# Schematic.net
KiCad netlist of a schematic drawn in EAGLE
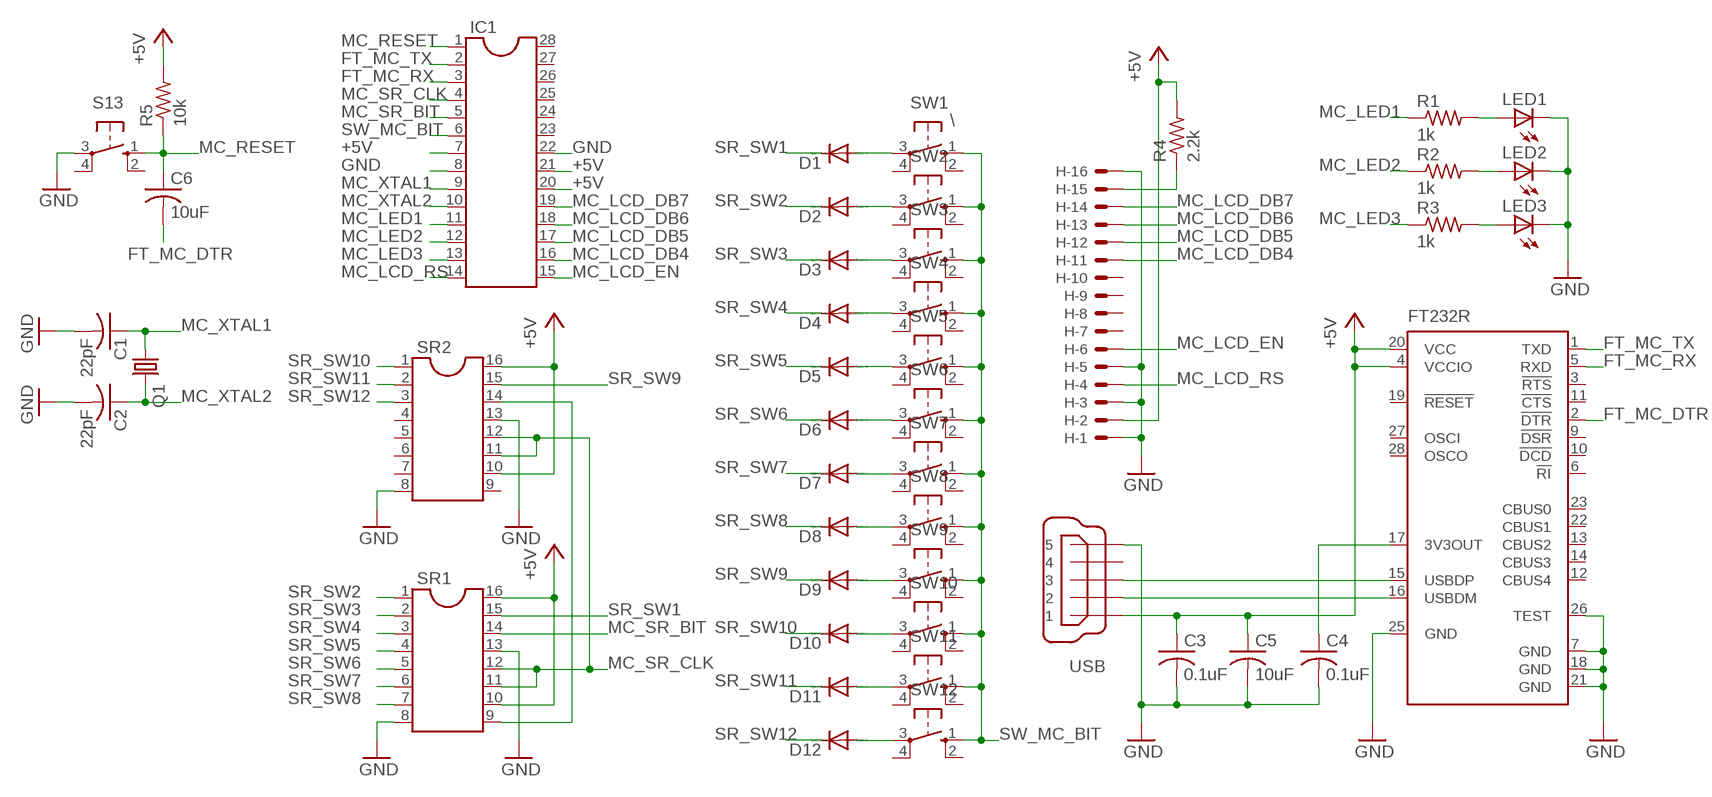
[diagram p0: schematic, sheet 1]

(export (version "E")
  (design (tool "Eeschema 10.0.6"))
  (components
    (comp (ref "C1")
      (value "22pF")
      (footprint "eagle-import:C025-024X044")
      (libsource (lib "eagle-import") (part "C-US025-024X044"))
    )
    (comp (ref "C2")
      (value "22pF")
      (footprint "eagle-import:C025-024X044")
      (libsource (lib "eagle-import") (part "C-US025-024X044"))
    )
    (comp (ref "C3")
      (value "0.1uF")
      (footprint "eagle-import:C025-024X044")
      (libsource (lib "eagle-import") (part "C-US025-024X044"))
    )
    (comp (ref "C4")
      (value "0.1uF")
      (footprint "eagle-import:C025-024X044")
      (libsource (lib "eagle-import") (part "C-US025-024X044"))
    )
    (comp (ref "C5")
      (value "10uF")
      (footprint "eagle-import:C025-024X044")
      (libsource (lib "eagle-import") (part "C-US025-024X044"))
    )
    (comp (ref "C6")
      (value "10uF")
      (footprint "eagle-import:C025-024X044")
      (libsource (lib "eagle-import") (part "C-US025-024X044"))
    )
    (comp (ref "D1")
      (value "DIODE-DO35-10")
      (footprint "eagle-import:DO35-10")
      (libsource (lib "eagle-import") (part "DIODE-DO35-10"))
    )
    (comp (ref "D2")
      (value "DIODE-DO35-10")
      (footprint "eagle-import:DO35-10")
      (libsource (lib "eagle-import") (part "DIODE-DO35-10"))
    )
    (comp (ref "D3")
      (value "DIODE-DO35-10")
      (footprint "eagle-import:DO35-10")
      (libsource (lib "eagle-import") (part "DIODE-DO35-10"))
    )
    (comp (ref "D4")
      (value "DIODE-DO35-10")
      (footprint "eagle-import:DO35-10")
      (libsource (lib "eagle-import") (part "DIODE-DO35-10"))
    )
    (comp (ref "D5")
      (value "DIODE-DO35-10")
      (footprint "eagle-import:DO35-10")
      (libsource (lib "eagle-import") (part "DIODE-DO35-10"))
    )
    (comp (ref "D6")
      (value "DIODE-DO35-10")
      (footprint "eagle-import:DO35-10")
      (libsource (lib "eagle-import") (part "DIODE-DO35-10"))
    )
    (comp (ref "D7")
      (value "DIODE-DO35-10")
      (footprint "eagle-import:DO35-10")
      (libsource (lib "eagle-import") (part "DIODE-DO35-10"))
    )
    (comp (ref "D8")
      (value "DIODE-DO35-10")
      (footprint "eagle-import:DO35-10")
      (libsource (lib "eagle-import") (part "DIODE-DO35-10"))
    )
    (comp (ref "D9")
      (value "DIODE-DO35-10")
      (footprint "eagle-import:DO35-10")
      (libsource (lib "eagle-import") (part "DIODE-DO35-10"))
    )
    (comp (ref "D10")
      (value "DIODE-DO35-10")
      (footprint "eagle-import:DO35-10")
      (libsource (lib "eagle-import") (part "DIODE-DO35-10"))
    )
    (comp (ref "D11")
      (value "DIODE-DO35-10")
      (footprint "eagle-import:DO35-10")
      (libsource (lib "eagle-import") (part "DIODE-DO35-10"))
    )
    (comp (ref "D12")
      (value "DIODE-DO35-10")
      (footprint "eagle-import:DO35-10")
      (libsource (lib "eagle-import") (part "DIODE-DO35-10"))
    )
    (comp (ref "FT232R")
      (value "FT232RL")
      (footprint "eagle-import:SSOP28")
      (libsource (lib "eagle-import") (part "FT232RL"))
    )
    (comp (ref "H")
      (value "C-GRID-16-70543")
      (footprint "eagle-import:70543-16")
      (libsource (lib "eagle-import") (part "C-GRID-16-70543"))
    )
    (comp (ref "IC1")
      (value "DIL28-3")
      (footprint "eagle-import:DIL28-3")
      (libsource (lib "eagle-import") (part "DIL28-3"))
    )
    (comp (ref "LED1")
      (value "LED3MM")
      (footprint "eagle-import:LED3MM")
      (libsource (lib "eagle-import") (part "LED3MM"))
    )
    (comp (ref "LED2")
      (value "LED3MM")
      (footprint "eagle-import:LED3MM")
      (libsource (lib "eagle-import") (part "LED3MM"))
    )
    (comp (ref "LED3")
      (value "LED3MM")
      (footprint "eagle-import:LED3MM")
      (libsource (lib "eagle-import") (part "LED3MM"))
    )
    (comp (ref "Q1")
      (value "CRYSTALHC49U-V")
      (footprint "eagle-import:HC49U-V")
      (libsource (lib "eagle-import") (part "CRYSTALHC49U-V"))
    )
    (comp (ref "R1")
      (value "1k")
      (footprint "eagle-import:0204V")
      (libsource (lib "eagle-import") (part "R-US_0204/2V"))
    )
    (comp (ref "R2")
      (value "1k")
      (footprint "eagle-import:0204V")
      (libsource (lib "eagle-import") (part "R-US_0204/2V"))
    )
    (comp (ref "R3")
      (value "1k")
      (footprint "eagle-import:0204V")
      (libsource (lib "eagle-import") (part "R-US_0204/2V"))
    )
    (comp (ref "R4")
      (value "2.2k")
      (footprint "eagle-import:0204V")
      (libsource (lib "eagle-import") (part "R-US_0204/2V"))
    )
    (comp (ref "R5")
      (value "10k")
      (footprint "eagle-import:0204V")
      (libsource (lib "eagle-import") (part "R-US_0204/2V"))
    )
    (comp (ref "S13")
      (value "10-XX")
      (footprint "eagle-import:B3F-10XX")
      (fields (field (name "MPN") "B3F-1000"))
      (libsource (lib "eagle-import") (part "10-XX"))
    )
    (comp (ref "SR1")
      (value "DIL16")
      (footprint "eagle-import:DIL16")
      (libsource (lib "eagle-import") (part "DIL16"))
    )
    (comp (ref "SR2")
      (value "DIL16")
      (footprint "eagle-import:DIL16")
      (libsource (lib "eagle-import") (part "DIL16"))
    )
    (comp (ref "SW1")
      (value "\\")
      (footprint "eagle-import:B3F-10XX")
      (fields (field (name "MPN") "B3F-1000"))
      (libsource (lib "eagle-import") (part "10-XX"))
    )
    (comp (ref "SW2")
      (value "10-XX")
      (footprint "eagle-import:B3F-10XX")
      (fields (field (name "MPN") "B3F-1000"))
      (libsource (lib "eagle-import") (part "10-XX"))
    )
    (comp (ref "SW3")
      (value "10-XX")
      (footprint "eagle-import:B3F-10XX")
      (fields (field (name "MPN") "B3F-1000"))
      (libsource (lib "eagle-import") (part "10-XX"))
    )
    (comp (ref "SW4")
      (value "10-XX")
      (footprint "eagle-import:B3F-10XX")
      (fields (field (name "MPN") "B3F-1000"))
      (libsource (lib "eagle-import") (part "10-XX"))
    )
    (comp (ref "SW5")
      (value "10-XX")
      (footprint "eagle-import:B3F-10XX")
      (fields (field (name "MPN") "B3F-1000"))
      (libsource (lib "eagle-import") (part "10-XX"))
    )
    (comp (ref "SW6")
      (value "10-XX")
      (footprint "eagle-import:B3F-10XX")
      (fields (field (name "MPN") "B3F-1000"))
      (libsource (lib "eagle-import") (part "10-XX"))
    )
    (comp (ref "SW7")
      (value "10-XX")
      (footprint "eagle-import:B3F-10XX")
      (fields (field (name "MPN") "B3F-1000"))
      (libsource (lib "eagle-import") (part "10-XX"))
    )
    (comp (ref "SW8")
      (value "10-XX")
      (footprint "eagle-import:B3F-10XX")
      (fields (field (name "MPN") "B3F-1000"))
      (libsource (lib "eagle-import") (part "10-XX"))
    )
    (comp (ref "SW9")
      (value "10-XX")
      (footprint "eagle-import:B3F-10XX")
      (fields (field (name "MPN") "B3F-1000"))
      (libsource (lib "eagle-import") (part "10-XX"))
    )
    (comp (ref "SW10")
      (value "10-XX")
      (footprint "eagle-import:B3F-10XX")
      (fields (field (name "MPN") "B3F-1000"))
      (libsource (lib "eagle-import") (part "10-XX"))
    )
    (comp (ref "SW11")
      (value "10-XX")
      (footprint "eagle-import:B3F-10XX")
      (fields (field (name "MPN") "B3F-1000"))
      (libsource (lib "eagle-import") (part "10-XX"))
    )
    (comp (ref "SW12")
      (value "10-XX")
      (footprint "eagle-import:B3F-10XX")
      (fields (field (name "MPN") "B3F-1000"))
      (libsource (lib "eagle-import") (part "10-XX"))
    )
    (comp (ref "USB")
      (value "MINI-USB_SHIELD5P2-32005-601")
      (footprint "eagle-import:32005-601")
      (libsource (lib "eagle-import") (part "MINI-USB_SHIELD5P2-32005-601"))
    )
  )
  (nets
    (net (code "1") (name "+5V") (class "Default")
      (node (ref "C3") (pin "1") (pinfunction "1_1") (pintype "passive"))
      (node (ref "C5") (pin "1") (pinfunction "1_1") (pintype "passive"))
      (node (ref "FT232R") (pin "20") (pinfunction "VCC_20") (pintype "power_in"))
      (node (ref "FT232R") (pin "4") (pinfunction "VCCIO_4") (pintype "power_in"))
      (node (ref "H") (pin "2") (pinfunction "S_2") (pintype "passive"))
      (node (ref "IC1") (pin "20") (pinfunction "20_20") (pintype "passive"))
      (node (ref "IC1") (pin "21") (pinfunction "21_21") (pintype "passive"))
      (node (ref "IC1") (pin "7") (pinfunction "7_7") (pintype "passive"))
      (node (ref "R4") (pin "2") (pinfunction "2_2") (pintype "passive"))
      (node (ref "R5") (pin "2") (pinfunction "2_2") (pintype "passive"))
      (node (ref "SR1") (pin "10") (pinfunction "10_10") (pintype "passive"))
      (node (ref "SR1") (pin "16") (pinfunction "16_16") (pintype "passive"))
      (node (ref "SR2") (pin "10") (pinfunction "10_10") (pintype "passive"))
      (node (ref "SR2") (pin "16") (pinfunction "16_16") (pintype "passive"))
      (node (ref "USB") (pin "1") (pinfunction "1_1") (pintype "passive"))
    )
    (net (code "2") (name "/FT_MC_DTR") (class "Default")
      (node (ref "C6") (pin "2") (pinfunction "2_2") (pintype "passive"))
      (node (ref "FT232R") (pin "2") (pinfunction "~{DTR}_2") (pintype "output"))
    )
    (net (code "3") (name "/FT_MC_RX") (class "Default")
      (node (ref "FT232R") (pin "5") (pinfunction "RXD_5") (pintype "input"))
      (node (ref "IC1") (pin "3") (pinfunction "3_3") (pintype "passive"))
    )
    (net (code "4") (name "/FT_MC_TX") (class "Default")
      (node (ref "FT232R") (pin "1") (pinfunction "TXD_1") (pintype "output"))
      (node (ref "IC1") (pin "2") (pinfunction "2_2") (pintype "passive"))
    )
    (net (code "5") (name "/MC_LCD_DB4") (class "Default")
      (node (ref "H") (pin "11") (pinfunction "S_11") (pintype "passive"))
      (node (ref "IC1") (pin "16") (pinfunction "16_16") (pintype "passive"))
    )
    (net (code "6") (name "/MC_LCD_DB5") (class "Default")
      (node (ref "H") (pin "12") (pinfunction "S_12") (pintype "passive"))
      (node (ref "IC1") (pin "17") (pinfunction "17_17") (pintype "passive"))
    )
    (net (code "7") (name "/MC_LCD_DB6") (class "Default")
      (node (ref "H") (pin "13") (pinfunction "S_13") (pintype "passive"))
      (node (ref "IC1") (pin "18") (pinfunction "18_18") (pintype "passive"))
    )
    (net (code "8") (name "/MC_LCD_DB7") (class "Default")
      (node (ref "H") (pin "14") (pinfunction "S_14") (pintype "passive"))
      (node (ref "IC1") (pin "19") (pinfunction "19_19") (pintype "passive"))
    )
    (net (code "9") (name "/MC_LCD_EN") (class "Default")
      (node (ref "H") (pin "6") (pinfunction "S_6") (pintype "passive"))
      (node (ref "IC1") (pin "15") (pinfunction "15_15") (pintype "passive"))
    )
    (net (code "10") (name "/MC_LCD_RS") (class "Default")
      (node (ref "H") (pin "4") (pinfunction "S_4") (pintype "passive"))
      (node (ref "IC1") (pin "14") (pinfunction "14_14") (pintype "passive"))
    )
    (net (code "11") (name "/MC_LED1") (class "Default")
      (node (ref "IC1") (pin "11") (pinfunction "11_11") (pintype "passive"))
      (node (ref "R1") (pin "1") (pinfunction "1_1") (pintype "passive"))
    )
    (net (code "12") (name "/MC_LED2") (class "Default")
      (node (ref "IC1") (pin "12") (pinfunction "12_12") (pintype "passive"))
      (node (ref "R2") (pin "1") (pinfunction "1_1") (pintype "passive"))
    )
    (net (code "13") (name "/MC_LED3") (class "Default")
      (node (ref "IC1") (pin "13") (pinfunction "13_13") (pintype "passive"))
      (node (ref "R3") (pin "1") (pinfunction "1_1") (pintype "passive"))
    )
    (net (code "14") (name "/MC_RESET") (class "Default")
      (node (ref "C6") (pin "1") (pinfunction "1_1") (pintype "passive"))
      (node (ref "IC1") (pin "1") (pinfunction "1_1") (pintype "passive"))
      (node (ref "R5") (pin "1") (pinfunction "1_1") (pintype "passive"))
      (node (ref "S13") (pin "1") (pinfunction "S_1") (pintype "passive"))
    )
    (net (code "15") (name "/MC_SR_BIT") (class "Default")
      (node (ref "IC1") (pin "5") (pinfunction "5_5") (pintype "passive"))
      (node (ref "SR1") (pin "14") (pinfunction "14_14") (pintype "passive"))
    )
    (net (code "16") (name "/MC_SR_CLK") (class "Default")
      (node (ref "IC1") (pin "4") (pinfunction "4_4") (pintype "passive"))
      (node (ref "SR1") (pin "11") (pinfunction "11_11") (pintype "passive"))
      (node (ref "SR1") (pin "12") (pinfunction "12_12") (pintype "passive"))
      (node (ref "SR2") (pin "11") (pinfunction "11_11") (pintype "passive"))
      (node (ref "SR2") (pin "12") (pinfunction "12_12") (pintype "passive"))
    )
    (net (code "17") (name "/MC_XTAL1") (class "Default")
      (node (ref "C1") (pin "1") (pinfunction "1_1") (pintype "passive"))
      (node (ref "IC1") (pin "9") (pinfunction "9_9") (pintype "passive"))
      (node (ref "Q1") (pin "1") (pinfunction "1_1") (pintype "passive"))
    )
    (net (code "18") (name "/MC_XTAL2") (class "Default")
      (node (ref "C2") (pin "1") (pinfunction "1_1") (pintype "passive"))
      (node (ref "IC1") (pin "10") (pinfunction "10_10") (pintype "passive"))
      (node (ref "Q1") (pin "2") (pinfunction "2_2") (pintype "passive"))
    )
    (net (code "19") (name "/SR_SW1") (class "Default")
      (node (ref "D1") (pin "C") (pinfunction "C_C") (pintype "passive"))
      (node (ref "SR1") (pin "15") (pinfunction "15_15") (pintype "passive"))
    )
    (net (code "20") (name "/SR_SW2") (class "Default")
      (node (ref "D2") (pin "C") (pinfunction "C_C") (pintype "passive"))
      (node (ref "SR1") (pin "1") (pinfunction "1_1") (pintype "passive"))
    )
    (net (code "21") (name "/SR_SW3") (class "Default")
      (node (ref "D3") (pin "C") (pinfunction "C_C") (pintype "passive"))
      (node (ref "SR1") (pin "2") (pinfunction "2_2") (pintype "passive"))
    )
    (net (code "22") (name "/SR_SW4") (class "Default")
      (node (ref "D4") (pin "C") (pinfunction "C_C") (pintype "passive"))
      (node (ref "SR1") (pin "3") (pinfunction "3_3") (pintype "passive"))
    )
    (net (code "23") (name "/SR_SW5") (class "Default")
      (node (ref "D5") (pin "C") (pinfunction "C_C") (pintype "passive"))
      (node (ref "SR1") (pin "4") (pinfunction "4_4") (pintype "passive"))
    )
    (net (code "24") (name "/SR_SW6") (class "Default")
      (node (ref "D6") (pin "C") (pinfunction "C_C") (pintype "passive"))
      (node (ref "SR1") (pin "5") (pinfunction "5_5") (pintype "passive"))
    )
    (net (code "25") (name "/SR_SW7") (class "Default")
      (node (ref "D7") (pin "C") (pinfunction "C_C") (pintype "passive"))
      (node (ref "SR1") (pin "6") (pinfunction "6_6") (pintype "passive"))
    )
    (net (code "26") (name "/SR_SW8") (class "Default")
      (node (ref "D8") (pin "C") (pinfunction "C_C") (pintype "passive"))
      (node (ref "SR1") (pin "7") (pinfunction "7_7") (pintype "passive"))
    )
    (net (code "27") (name "/SR_SW9") (class "Default")
      (node (ref "D9") (pin "C") (pinfunction "C_C") (pintype "passive"))
      (node (ref "SR2") (pin "15") (pinfunction "15_15") (pintype "passive"))
    )
    (net (code "28") (name "/SR_SW10") (class "Default")
      (node (ref "D10") (pin "C") (pinfunction "C_C") (pintype "passive"))
      (node (ref "SR2") (pin "1") (pinfunction "1_1") (pintype "passive"))
    )
    (net (code "29") (name "/SR_SW11") (class "Default")
      (node (ref "D11") (pin "C") (pinfunction "C_C") (pintype "passive"))
      (node (ref "SR2") (pin "2") (pinfunction "2_2") (pintype "passive"))
    )
    (net (code "30") (name "/SR_SW12") (class "Default")
      (node (ref "D12") (pin "C") (pinfunction "C_C") (pintype "passive"))
      (node (ref "SR2") (pin "3") (pinfunction "3_3") (pintype "passive"))
    )
    (net (code "31") (name "/SW_MC_BIT") (class "Default")
      (node (ref "IC1") (pin "6") (pinfunction "6_6") (pintype "passive"))
      (node (ref "SW1") (pin "1") (pinfunction "S_1") (pintype "passive"))
      (node (ref "SW10") (pin "1") (pinfunction "S_1") (pintype "passive"))
      (node (ref "SW11") (pin "1") (pinfunction "S_1") (pintype "passive"))
      (node (ref "SW12") (pin "1") (pinfunction "S_1") (pintype "passive"))
      (node (ref "SW2") (pin "1") (pinfunction "S_1") (pintype "passive"))
      (node (ref "SW3") (pin "1") (pinfunction "S_1") (pintype "passive"))
      (node (ref "SW4") (pin "1") (pinfunction "S_1") (pintype "passive"))
      (node (ref "SW5") (pin "1") (pinfunction "S_1") (pintype "passive"))
      (node (ref "SW6") (pin "1") (pinfunction "S_1") (pintype "passive"))
      (node (ref "SW7") (pin "1") (pinfunction "S_1") (pintype "passive"))
      (node (ref "SW8") (pin "1") (pinfunction "S_1") (pintype "passive"))
      (node (ref "SW9") (pin "1") (pinfunction "S_1") (pintype "passive"))
    )
    (net (code "32") (name "GND") (class "Default")
      (node (ref "C1") (pin "2") (pinfunction "2_2") (pintype "passive"))
      (node (ref "C2") (pin "2") (pinfunction "2_2") (pintype "passive"))
      (node (ref "C3") (pin "2") (pinfunction "2_2") (pintype "passive"))
      (node (ref "C4") (pin "2") (pinfunction "2_2") (pintype "passive"))
      (node (ref "C5") (pin "2") (pinfunction "2_2") (pintype "passive"))
      (node (ref "FT232R") (pin "18") (pinfunction "GND_18") (pintype "power_in"))
      (node (ref "FT232R") (pin "21") (pinfunction "GND_21") (pintype "power_in"))
      (node (ref "FT232R") (pin "25") (pinfunction "GND_25") (pintype "power_in"))
      (node (ref "FT232R") (pin "26") (pinfunction "TEST_26") (pintype "input"))
      (node (ref "FT232R") (pin "7") (pinfunction "GND_7") (pintype "power_in"))
      (node (ref "H") (pin "1") (pinfunction "S_1") (pintype "passive"))
      (node (ref "H") (pin "16") (pinfunction "S_16") (pintype "passive"))
      (node (ref "H") (pin "3") (pinfunction "S_3") (pintype "passive"))
      (node (ref "H") (pin "5") (pinfunction "S_5") (pintype "passive"))
      (node (ref "IC1") (pin "22") (pinfunction "22_22") (pintype "passive"))
      (node (ref "IC1") (pin "8") (pinfunction "8_8") (pintype "passive"))
      (node (ref "LED1") (pin "K") (pinfunction "C_K") (pintype "passive"))
      (node (ref "LED2") (pin "K") (pinfunction "C_K") (pintype "passive"))
      (node (ref "LED3") (pin "K") (pinfunction "C_K") (pintype "passive"))
      (node (ref "S13") (pin "3") (pinfunction "P_3") (pintype "passive"))
      (node (ref "SR1") (pin "13") (pinfunction "13_13") (pintype "passive"))
      (node (ref "SR1") (pin "8") (pinfunction "8_8") (pintype "passive"))
      (node (ref "SR2") (pin "13") (pinfunction "13_13") (pintype "passive"))
      (node (ref "SR2") (pin "8") (pinfunction "8_8") (pintype "passive"))
      (node (ref "USB") (pin "5") (pinfunction "5_5") (pintype "passive"))
    )
    (net (code "33") (name "Net-(FT232R-3V3OUT)") (class "Default")
      (node (ref "C4") (pin "1") (pinfunction "1_1") (pintype "passive"))
      (node (ref "FT232R") (pin "17") (pinfunction "3V3OUT_17") (pintype "output"))
    )
    (net (code "34") (name "Net-(FT232R-USBDM)") (class "Default")
      (node (ref "FT232R") (pin "16") (pinfunction "USBDM_16") (pintype "bidirectional"))
      (node (ref "USB") (pin "2") (pinfunction "2_2") (pintype "passive"))
    )
    (net (code "35") (name "Net-(FT232R-USBDP)") (class "Default")
      (node (ref "FT232R") (pin "15") (pinfunction "USBDP_15") (pintype "bidirectional"))
      (node (ref "USB") (pin "3") (pinfunction "3_3") (pintype "passive"))
    )
    (net (code "36") (name "Net-(HG-S)") (class "Default")
      (node (ref "H") (pin "15") (pinfunction "S_15") (pintype "passive"))
      (node (ref "R4") (pin "1") (pinfunction "1_1") (pintype "passive"))
    )
    (net (code "37") (name "Net-(LED1-PadA)") (class "Default")
      (node (ref "LED1") (pin "A") (pinfunction "A_A") (pintype "passive"))
      (node (ref "R1") (pin "2") (pinfunction "2_2") (pintype "passive"))
    )
    (net (code "38") (name "Net-(LED2-PadA)") (class "Default")
      (node (ref "LED2") (pin "A") (pinfunction "A_A") (pintype "passive"))
      (node (ref "R2") (pin "2") (pinfunction "2_2") (pintype "passive"))
    )
    (net (code "39") (name "Net-(LED3-PadA)") (class "Default")
      (node (ref "LED3") (pin "A") (pinfunction "A_A") (pintype "passive"))
      (node (ref "R3") (pin "2") (pinfunction "2_2") (pintype "passive"))
    )
    (net (code "40") (name "Net-(SR1-Pad9)") (class "Default")
      (node (ref "SR1") (pin "9") (pinfunction "9_9") (pintype "passive"))
      (node (ref "SR2") (pin "14") (pinfunction "14_14") (pintype "passive"))
    )
    (net (code "41") (name "Net-(SW1-P)") (class "Default")
      (node (ref "D1") (pin "A") (pinfunction "A_A") (pintype "passive"))
      (node (ref "SW1") (pin "3") (pinfunction "P_3") (pintype "passive"))
    )
    (net (code "42") (name "Net-(SW2-P)") (class "Default")
      (node (ref "D2") (pin "A") (pinfunction "A_A") (pintype "passive"))
      (node (ref "SW2") (pin "3") (pinfunction "P_3") (pintype "passive"))
    )
    (net (code "43") (name "Net-(SW3-P)") (class "Default")
      (node (ref "D3") (pin "A") (pinfunction "A_A") (pintype "passive"))
      (node (ref "SW3") (pin "3") (pinfunction "P_3") (pintype "passive"))
    )
    (net (code "44") (name "Net-(SW4-P)") (class "Default")
      (node (ref "D4") (pin "A") (pinfunction "A_A") (pintype "passive"))
      (node (ref "SW4") (pin "3") (pinfunction "P_3") (pintype "passive"))
    )
    (net (code "45") (name "Net-(SW5-P)") (class "Default")
      (node (ref "D5") (pin "A") (pinfunction "A_A") (pintype "passive"))
      (node (ref "SW5") (pin "3") (pinfunction "P_3") (pintype "passive"))
    )
    (net (code "46") (name "Net-(SW6-P)") (class "Default")
      (node (ref "D6") (pin "A") (pinfunction "A_A") (pintype "passive"))
      (node (ref "SW6") (pin "3") (pinfunction "P_3") (pintype "passive"))
    )
    (net (code "47") (name "Net-(SW7-P)") (class "Default")
      (node (ref "D7") (pin "A") (pinfunction "A_A") (pintype "passive"))
      (node (ref "SW7") (pin "3") (pinfunction "P_3") (pintype "passive"))
    )
    (net (code "48") (name "Net-(SW8-P)") (class "Default")
      (node (ref "D8") (pin "A") (pinfunction "A_A") (pintype "passive"))
      (node (ref "SW8") (pin "3") (pinfunction "P_3") (pintype "passive"))
    )
    (net (code "49") (name "Net-(SW9-P)") (class "Default")
      (node (ref "D9") (pin "A") (pinfunction "A_A") (pintype "passive"))
      (node (ref "SW9") (pin "3") (pinfunction "P_3") (pintype "passive"))
    )
    (net (code "50") (name "Net-(SW10-P)") (class "Default")
      (node (ref "D10") (pin "A") (pinfunction "A_A") (pintype "passive"))
      (node (ref "SW10") (pin "3") (pinfunction "P_3") (pintype "passive"))
    )
    (net (code "51") (name "Net-(SW11-P)") (class "Default")
      (node (ref "D11") (pin "A") (pinfunction "A_A") (pintype "passive"))
      (node (ref "SW11") (pin "3") (pinfunction "P_3") (pintype "passive"))
    )
    (net (code "52") (name "Net-(SW12-P)") (class "Default")
      (node (ref "D12") (pin "A") (pinfunction "A_A") (pintype "passive"))
      (node (ref "SW12") (pin "3") (pinfunction "P_3") (pintype "passive"))
    )
    (net (code "53") (name "unconnected-(FT232R-CBUS0-Pad23)") (class "Default")
      (node (ref "FT232R") (pin "23") (pinfunction "CBUS0_23") (pintype "bidirectional"))
    )
    (net (code "54") (name "unconnected-(FT232R-CBUS1-Pad22)") (class "Default")
      (node (ref "FT232R") (pin "22") (pinfunction "CBUS1_22") (pintype "bidirectional"))
    )
    (net (code "55") (name "unconnected-(FT232R-CBUS2-Pad13)") (class "Default")
      (node (ref "FT232R") (pin "13") (pinfunction "CBUS2_13") (pintype "bidirectional"))
    )
    (net (code "56") (name "unconnected-(FT232R-CBUS3-Pad14)") (class "Default")
      (node (ref "FT232R") (pin "14") (pinfunction "CBUS3_14") (pintype "bidirectional"))
    )
    (net (code "57") (name "unconnected-(FT232R-CBUS4-Pad12)") (class "Default")
      (node (ref "FT232R") (pin "12") (pinfunction "CBUS4_12") (pintype "bidirectional"))
    )
    (net (code "58") (name "unconnected-(FT232R-OSCI-Pad27)") (class "Default")
      (node (ref "FT232R") (pin "27") (pinfunction "OSCI_27") (pintype "input"))
    )
    (net (code "59") (name "unconnected-(FT232R-OSCO-Pad28)") (class "Default")
      (node (ref "FT232R") (pin "28") (pinfunction "OSCO_28") (pintype "output"))
    )
    (net (code "60") (name "unconnected-(FT232R-~{CTS}-Pad11)") (class "Default")
      (node (ref "FT232R") (pin "11") (pinfunction "~{CTS}_11") (pintype "input"))
    )
    (net (code "61") (name "unconnected-(FT232R-~{DCD}-Pad10)") (class "Default")
      (node (ref "FT232R") (pin "10") (pinfunction "~{DCD}_10") (pintype "input"))
    )
    (net (code "62") (name "unconnected-(FT232R-~{DSR}-Pad9)") (class "Default")
      (node (ref "FT232R") (pin "9") (pinfunction "~{DSR}_9") (pintype "input"))
    )
    (net (code "63") (name "unconnected-(FT232R-~{RESET}-Pad19)") (class "Default")
      (node (ref "FT232R") (pin "19") (pinfunction "~{RESET}_19") (pintype "input"))
    )
    (net (code "64") (name "unconnected-(FT232R-~{RI}-Pad6)") (class "Default")
      (node (ref "FT232R") (pin "6") (pinfunction "~{RI}_6") (pintype "input"))
    )
    (net (code "65") (name "unconnected-(FT232R-~{RTS}-Pad3)") (class "Default")
      (node (ref "FT232R") (pin "3") (pinfunction "~{RTS}_3") (pintype "output"))
    )
    (net (code "66") (name "unconnected-(HB-S-Pad10)") (class "Default")
      (node (ref "H") (pin "10") (pinfunction "S_10") (pintype "passive"))
    )
    (net (code "67") (name "unconnected-(HN-S-Pad7)") (class "Default")
      (node (ref "H") (pin "7") (pinfunction "S_7") (pintype "passive"))
    )
    (net (code "68") (name "unconnected-(HO-S-Pad8)") (class "Default")
      (node (ref "H") (pin "8") (pinfunction "S_8") (pintype "passive"))
    )
    (net (code "69") (name "unconnected-(HP-S-Pad9)") (class "Default")
      (node (ref "H") (pin "9") (pinfunction "S_9") (pintype "passive"))
    )
    (net (code "70") (name "unconnected-(IC1-Pad23)") (class "Default")
      (node (ref "IC1") (pin "23") (pinfunction "23_23") (pintype "passive"))
    )
    (net (code "71") (name "unconnected-(IC1-Pad24)") (class "Default")
      (node (ref "IC1") (pin "24") (pinfunction "24_24") (pintype "passive"))
    )
    (net (code "72") (name "unconnected-(IC1-Pad25)") (class "Default")
      (node (ref "IC1") (pin "25") (pinfunction "25_25") (pintype "passive"))
    )
    (net (code "73") (name "unconnected-(IC1-Pad26)") (class "Default")
      (node (ref "IC1") (pin "26") (pinfunction "26_26") (pintype "passive"))
    )
    (net (code "74") (name "unconnected-(IC1-Pad27)") (class "Default")
      (node (ref "IC1") (pin "27") (pinfunction "27_27") (pintype "passive"))
    )
    (net (code "75") (name "unconnected-(IC1-Pad28)") (class "Default")
      (node (ref "IC1") (pin "28") (pinfunction "28_28") (pintype "passive"))
    )
    (net (code "76") (name "unconnected-(S13-P1-Pad4)") (class "Default")
      (node (ref "S13") (pin "4") (pinfunction "P1_4") (pintype "passive"))
    )
    (net (code "77") (name "unconnected-(S13-S1-Pad2)") (class "Default")
      (node (ref "S13") (pin "2") (pinfunction "S1_2") (pintype "passive"))
    )
    (net (code "78") (name "unconnected-(SR2-Pad4)") (class "Default")
      (node (ref "SR2") (pin "4") (pinfunction "4_4") (pintype "passive"))
    )
    (net (code "79") (name "unconnected-(SR2-Pad5)") (class "Default")
      (node (ref "SR2") (pin "5") (pinfunction "5_5") (pintype "passive"))
    )
    (net (code "80") (name "unconnected-(SR2-Pad6)") (class "Default")
      (node (ref "SR2") (pin "6") (pinfunction "6_6") (pintype "passive"))
    )
    (net (code "81") (name "unconnected-(SR2-Pad7)") (class "Default")
      (node (ref "SR2") (pin "7") (pinfunction "7_7") (pintype "passive"))
    )
    (net (code "82") (name "unconnected-(SR2-Pad9)") (class "Default")
      (node (ref "SR2") (pin "9") (pinfunction "9_9") (pintype "passive"))
    )
    (net (code "83") (name "unconnected-(SW1-P1-Pad4)") (class "Default")
      (node (ref "SW1") (pin "4") (pinfunction "P1_4") (pintype "passive"))
    )
    (net (code "84") (name "unconnected-(SW1-S1-Pad2)") (class "Default")
      (node (ref "SW1") (pin "2") (pinfunction "S1_2") (pintype "passive"))
    )
    (net (code "85") (name "unconnected-(SW2-P1-Pad4)") (class "Default")
      (node (ref "SW2") (pin "4") (pinfunction "P1_4") (pintype "passive"))
    )
    (net (code "86") (name "unconnected-(SW2-S1-Pad2)") (class "Default")
      (node (ref "SW2") (pin "2") (pinfunction "S1_2") (pintype "passive"))
    )
    (net (code "87") (name "unconnected-(SW3-P1-Pad4)") (class "Default")
      (node (ref "SW3") (pin "4") (pinfunction "P1_4") (pintype "passive"))
    )
    (net (code "88") (name "unconnected-(SW3-S1-Pad2)") (class "Default")
      (node (ref "SW3") (pin "2") (pinfunction "S1_2") (pintype "passive"))
    )
    (net (code "89") (name "unconnected-(SW4-P1-Pad4)") (class "Default")
      (node (ref "SW4") (pin "4") (pinfunction "P1_4") (pintype "passive"))
    )
    (net (code "90") (name "unconnected-(SW4-S1-Pad2)") (class "Default")
      (node (ref "SW4") (pin "2") (pinfunction "S1_2") (pintype "passive"))
    )
    (net (code "91") (name "unconnected-(SW5-P1-Pad4)") (class "Default")
      (node (ref "SW5") (pin "4") (pinfunction "P1_4") (pintype "passive"))
    )
    (net (code "92") (name "unconnected-(SW5-S1-Pad2)") (class "Default")
      (node (ref "SW5") (pin "2") (pinfunction "S1_2") (pintype "passive"))
    )
    (net (code "93") (name "unconnected-(SW6-P1-Pad4)") (class "Default")
      (node (ref "SW6") (pin "4") (pinfunction "P1_4") (pintype "passive"))
    )
    (net (code "94") (name "unconnected-(SW6-S1-Pad2)") (class "Default")
      (node (ref "SW6") (pin "2") (pinfunction "S1_2") (pintype "passive"))
    )
    (net (code "95") (name "unconnected-(SW7-P1-Pad4)") (class "Default")
      (node (ref "SW7") (pin "4") (pinfunction "P1_4") (pintype "passive"))
    )
    (net (code "96") (name "unconnected-(SW7-S1-Pad2)") (class "Default")
      (node (ref "SW7") (pin "2") (pinfunction "S1_2") (pintype "passive"))
    )
    (net (code "97") (name "unconnected-(SW8-P1-Pad4)") (class "Default")
      (node (ref "SW8") (pin "4") (pinfunction "P1_4") (pintype "passive"))
    )
    (net (code "98") (name "unconnected-(SW8-S1-Pad2)") (class "Default")
      (node (ref "SW8") (pin "2") (pinfunction "S1_2") (pintype "passive"))
    )
    (net (code "99") (name "unconnected-(SW9-P1-Pad4)") (class "Default")
      (node (ref "SW9") (pin "4") (pinfunction "P1_4") (pintype "passive"))
    )
    (net (code "100") (name "unconnected-(SW9-S1-Pad2)") (class "Default")
      (node (ref "SW9") (pin "2") (pinfunction "S1_2") (pintype "passive"))
    )
    (net (code "101") (name "unconnected-(SW10-P1-Pad4)") (class "Default")
      (node (ref "SW10") (pin "4") (pinfunction "P1_4") (pintype "passive"))
    )
    (net (code "102") (name "unconnected-(SW10-S1-Pad2)") (class "Default")
      (node (ref "SW10") (pin "2") (pinfunction "S1_2") (pintype "passive"))
    )
    (net (code "103") (name "unconnected-(SW11-P1-Pad4)") (class "Default")
      (node (ref "SW11") (pin "4") (pinfunction "P1_4") (pintype "passive"))
    )
    (net (code "104") (name "unconnected-(SW11-S1-Pad2)") (class "Default")
      (node (ref "SW11") (pin "2") (pinfunction "S1_2") (pintype "passive"))
    )
    (net (code "105") (name "unconnected-(SW12-P1-Pad4)") (class "Default")
      (node (ref "SW12") (pin "4") (pinfunction "P1_4") (pintype "passive"))
    )
    (net (code "106") (name "unconnected-(SW12-S1-Pad2)") (class "Default")
      (node (ref "SW12") (pin "2") (pinfunction "S1_2") (pintype "passive"))
    )
    (net (code "107") (name "unconnected-(USB-Pad4)") (class "Default")
      (node (ref "USB") (pin "4") (pinfunction "4_4") (pintype "passive"))
    )
  )
)
